# ASR-2DF.net
KiCad netlist of a schematic drawn in Altium Designer
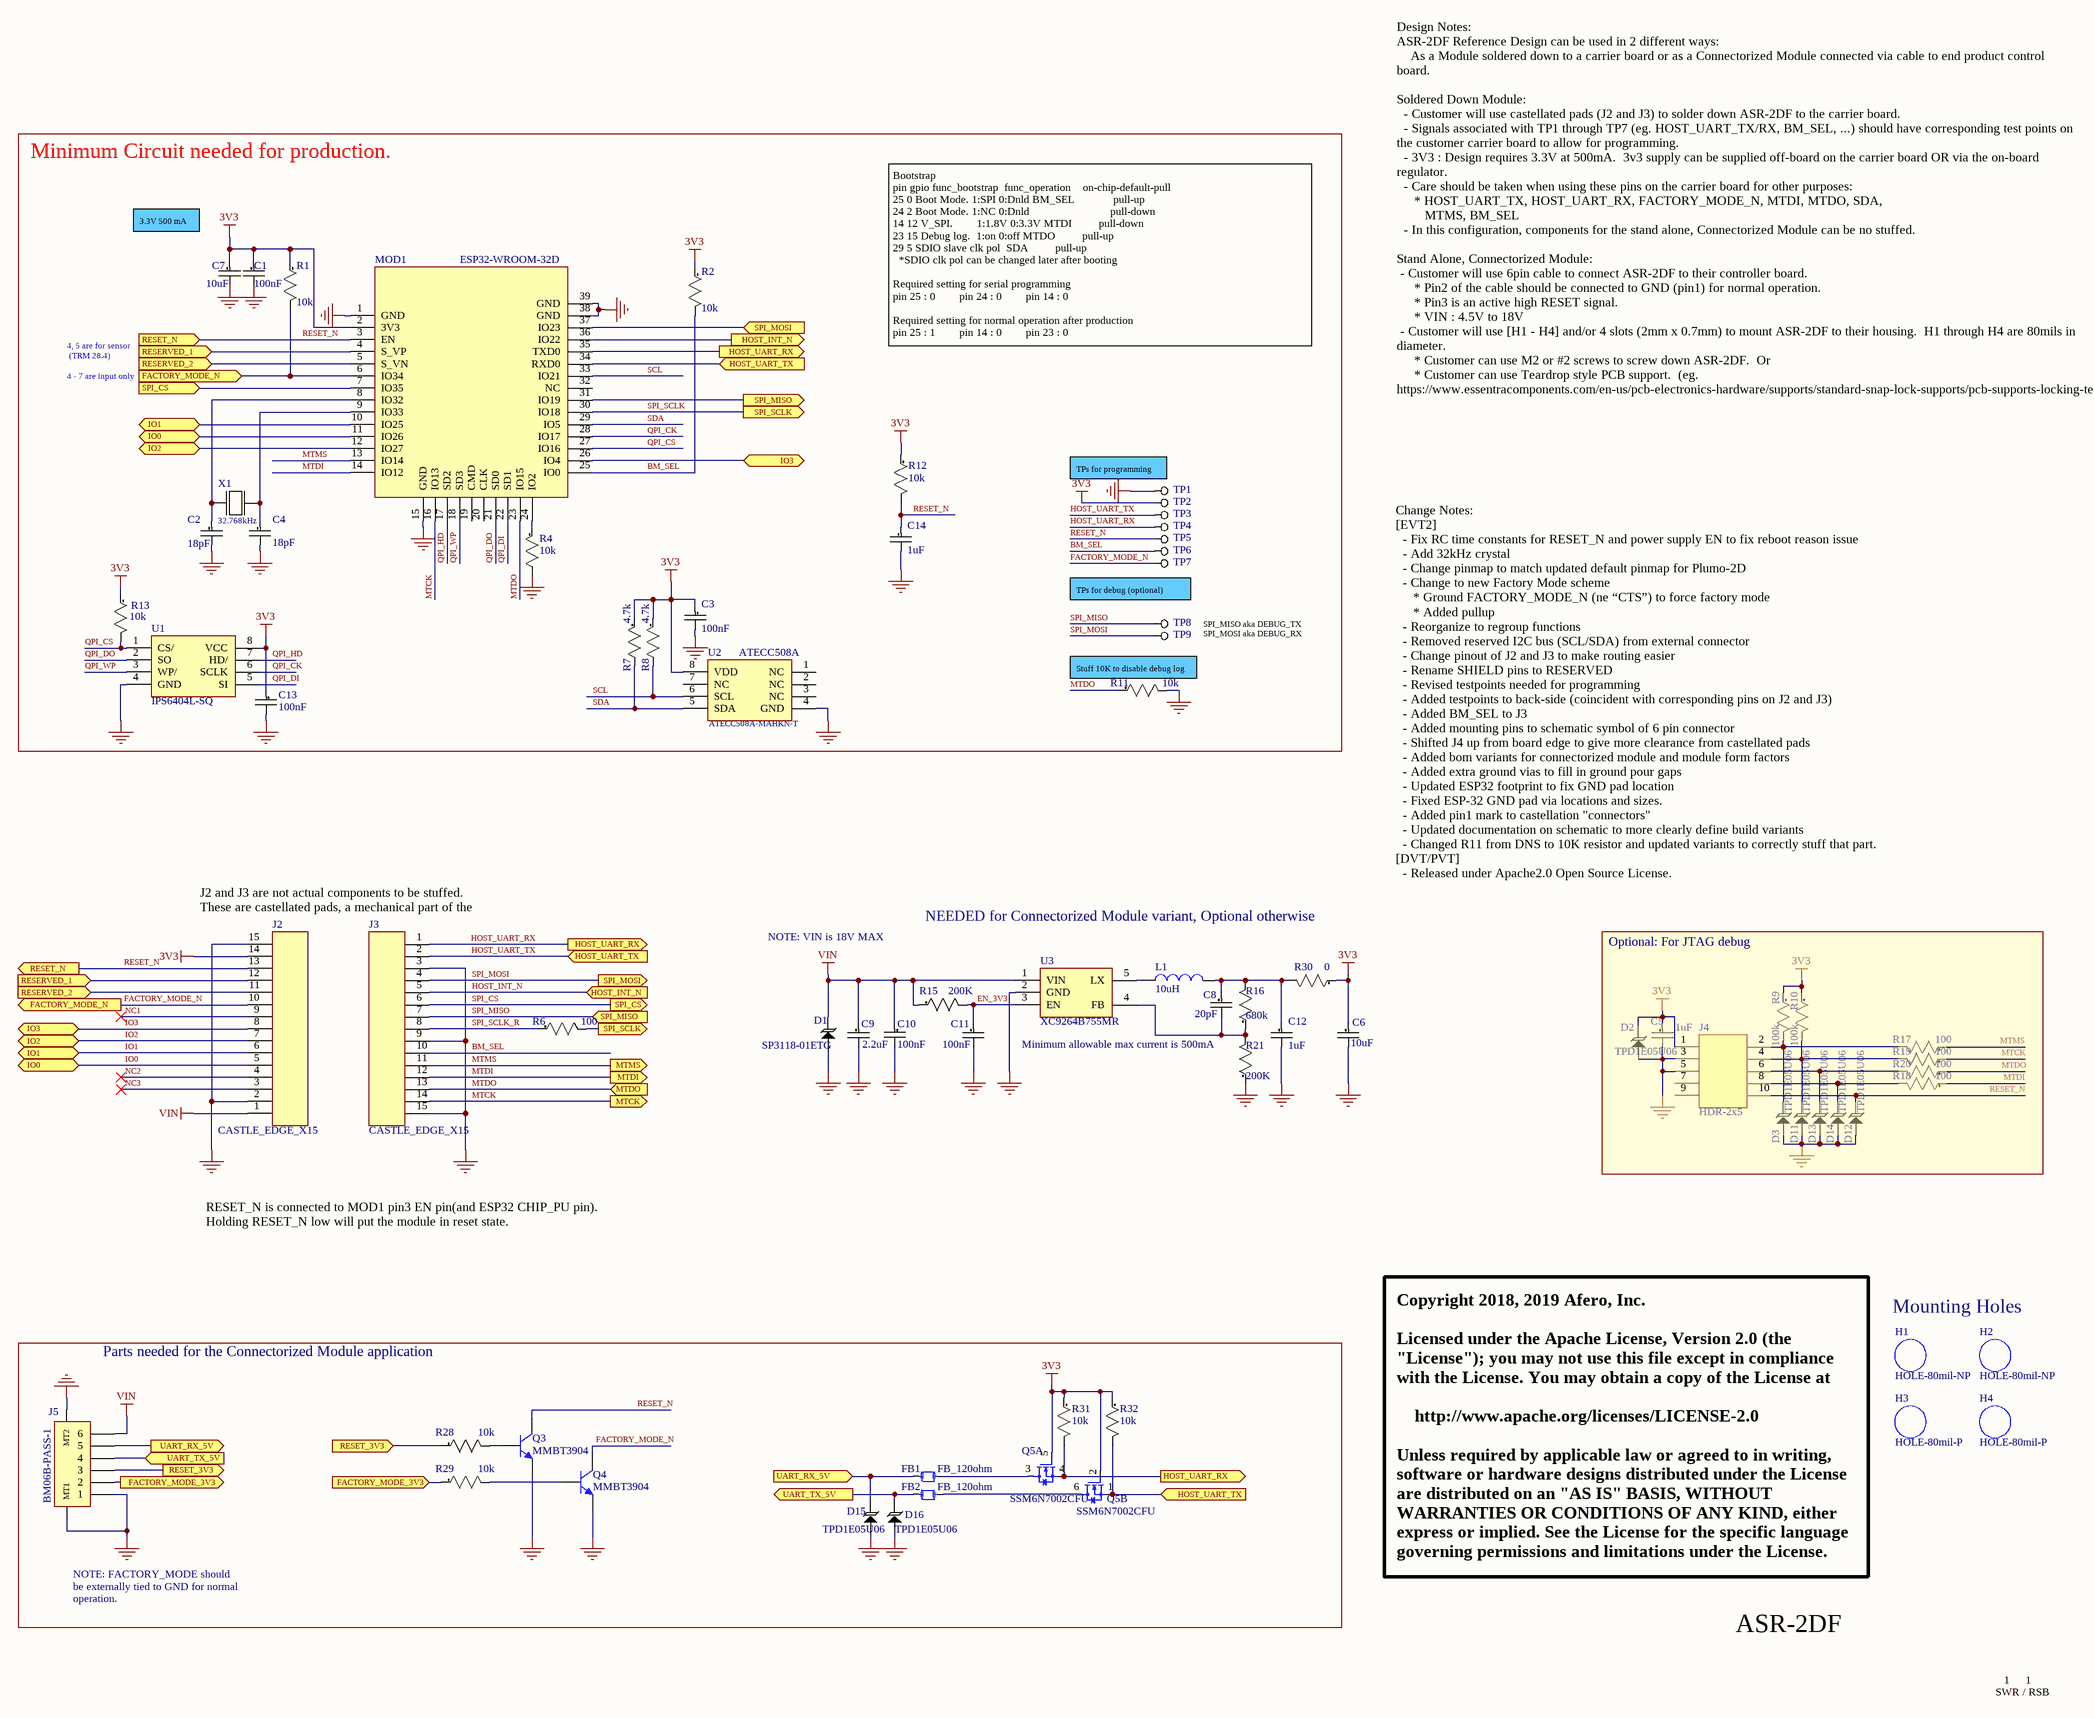
[diagram p0: ASR-2DF.SchDoc]

(export (version "E")
  (design (tool "Eeschema 10.0.6"))
  (components
    (comp (ref "C1")
      (value "100nF")
      (footprint "0402C-GENERIC")
      (description "Capacitor 100nF X5R 50V 10% 0402")
      (fields
        (field (name "MANUFACTURER") "Murata")
        (field (name "MANUFACTURER PART NUMBER") "GRM155R61H104KE19D")
      )
      (libsource (lib "ASR-2DF") (part "0402C-100n"))
    )
    (comp (ref "C2")
      (value "18pF")
      (footprint "0402C-GENERIC")
      (description "Capacitor, 18pF, 50V, 1%, C0G")
      (fields
        (field (name "MANUFACTURER") "Murata")
        (field (name "MANUFACTURER PART NUMBER") "GJM1555C1H180FB01D")
      )
      (libsource (lib "ASR-2DF") (part "0402C-18p"))
    )
    (comp (ref "C3")
      (value "100nF")
      (footprint "0402C-GENERIC")
      (description "Capacitor 100nF X5R 50V 10% 0402")
      (fields
        (field (name "MANUFACTURER") "Murata")
        (field (name "MANUFACTURER PART NUMBER") "GRM155R61H104KE19D")
      )
      (libsource (lib "ASR-2DF") (part "0402C-100n"))
    )
    (comp (ref "C4")
      (value "18pF")
      (footprint "0402C-GENERIC")
      (description "Capacitor, 18pF, 50V, 1%, C0G")
      (fields
        (field (name "MANUFACTURER") "Murata")
        (field (name "MANUFACTURER PART NUMBER") "GJM1555C1H180FB01D")
      )
      (libsource (lib "ASR-2DF") (part "0402C-18p"))
    )
    (comp (ref "C5")
      (value "1uF")
      (footprint "0402C-GENERIC")
      (description "Capacitor 1uF X5R 6.3V 20% 0402")
      (fields (field (name "MANUFACTURER") "SEM") (field (name "MANUFACTURER PART NUMBER") "CL05A105KQ5NNNC"))
      (libsource (lib "ASR-2DF") (part "0402C-1u"))
    )
    (comp (ref "C6")
      (value "10uF")
      (footprint "0603C-GENERIC")
      (description "Capacitor 10uF X5R 16V 20% 0603")
      (fields
        (field (name "MANUFACTURER") "Murata")
        (field (name "MANUFACTURER PART NUMBER") "GRM188R61C106MA73D")
      )
      (libsource (lib "ASR-2DF") (part "0603C-10u"))
    )
    (comp (ref "C7")
      (value "10uF")
      (footprint "0603C-GENERIC")
      (description "Capacitor 10uF X5R 16V 20% 0603")
      (fields
        (field (name "MANUFACTURER") "Murata")
        (field (name "MANUFACTURER PART NUMBER") "GRM188R61C106MA73D")
      )
      (libsource (lib "ASR-2DF") (part "0603C-10u"))
    )
    (comp (ref "C8")
      (value "20pF")
      (footprint "0402C-GENERIC")
      (description "Capacitor 20pF C0G 50V 1% 0402")
      (fields
        (field (name "MANUFACTURER") "Murata")
        (field (name "MANUFACTURER PART NUMBER") "GJM1555C1H200FB01D")
      )
      (libsource (lib "ASR-2DF") (part "0402C-20p"))
    )
    (comp (ref "C9")
      (value "2.2uF")
      (footprint "0603C-GENERIC")
      (description "Capacitor 2.2uF X5R 25V 10% 0603")
      (fields
        (field (name "MANUFACTURER") "Murata")
        (field (name "MANUFACTURER PART NUMBER") "GRM188R61E225KA12D")
      )
      (libsource (lib "ASR-2DF") (part "0603C-2u2"))
    )
    (comp (ref "C10")
      (value "100nF")
      (footprint "0402C-GENERIC")
      (description "Capacitor 100nF X5R 50V 10% 0402")
      (fields
        (field (name "MANUFACTURER") "Murata")
        (field (name "MANUFACTURER PART NUMBER") "GRM155R61H104KE19D")
      )
      (libsource (lib "ASR-2DF") (part "0402C-100n"))
    )
    (comp (ref "C11")
      (value "100nF")
      (footprint "0402C-GENERIC")
      (description "Capacitor 100nF X5R 50V 10% 0402")
      (fields
        (field (name "MANUFACTURER") "Murata")
        (field (name "MANUFACTURER PART NUMBER") "GRM155R61H104KE19D")
      )
      (libsource (lib "ASR-2DF") (part "0402C-100n"))
    )
    (comp (ref "C12")
      (value "1uF")
      (footprint "0402C-GENERIC")
      (description "Capacitor 1uF X5R 6.3V 20% 0402")
      (fields (field (name "MANUFACTURER") "SEM") (field (name "MANUFACTURER PART NUMBER") "CL05A105KQ5NNNC"))
      (libsource (lib "ASR-2DF") (part "0402C-1u"))
    )
    (comp (ref "C13")
      (value "100nF")
      (footprint "0402C-GENERIC")
      (description "Capacitor 100nF X5R 50V 10% 0402")
      (fields
        (field (name "MANUFACTURER") "Murata")
        (field (name "MANUFACTURER PART NUMBER") "GRM155R61H104KE19D")
      )
      (libsource (lib "ASR-2DF") (part "0402C-100n"))
    )
    (comp (ref "C14")
      (value "1uF")
      (footprint "0402C-GENERIC")
      (description "Capacitor 1uF X5R 6.3V 20% 0402")
      (fields (field (name "MANUFACTURER") "SEM") (field (name "MANUFACTURER PART NUMBER") "CL05A105KQ5NNNC"))
      (libsource (lib "ASR-2DF") (part "0402C-1u"))
    )
    (comp (ref "D1")
      (value "SP3118-01ETG")
      (footprint "SOD882")
      (description "Diode TVS")
      (fields (field (name "MANUFACTURER") "Littelfuse"))
      (libsource (lib "ASR-2DF") (part "SP3118-01ETG"))
    )
    (comp (ref "D2")
      (value "TPD1E05U06")
      (footprint "SON70P100X45-2N")
      (description "Diode TVS")
      (fields
        (field (name "MANUFACTURER") "Texas Instruments")
        (field (name "MANUFACTURER PART NUMBER") "TPD1E05U06DPYR")
      )
      (libsource (lib "ASR-2DF") (part "TPD1E05U06"))
    )
    (comp (ref "D3")
      (value "TPD1E05U06")
      (footprint "SON70P100X45-2N")
      (description "Diode TVS")
      (fields
        (field (name "MANUFACTURER") "Texas Instruments")
        (field (name "MANUFACTURER PART NUMBER") "TPD1E05U06DPYR")
      )
      (libsource (lib "ASR-2DF") (part "TPD1E05U06"))
    )
    (comp (ref "D11")
      (value "TPD1E05U06")
      (footprint "SON70P100X45-2N")
      (description "Diode TVS")
      (fields
        (field (name "MANUFACTURER") "Texas Instruments")
        (field (name "MANUFACTURER PART NUMBER") "TPD1E05U06DPYR")
      )
      (libsource (lib "ASR-2DF") (part "TPD1E05U06"))
    )
    (comp (ref "D12")
      (value "TPD1E05U06")
      (footprint "SON70P100X45-2N")
      (description "Diode TVS")
      (fields
        (field (name "MANUFACTURER") "Texas Instruments")
        (field (name "MANUFACTURER PART NUMBER") "TPD1E05U06DPYR")
      )
      (libsource (lib "ASR-2DF") (part "TPD1E05U06"))
    )
    (comp (ref "D13")
      (value "TPD1E05U06")
      (footprint "SON70P100X45-2N")
      (description "Diode TVS")
      (fields
        (field (name "MANUFACTURER") "Texas Instruments")
        (field (name "MANUFACTURER PART NUMBER") "TPD1E05U06DPYR")
      )
      (libsource (lib "ASR-2DF") (part "TPD1E05U06"))
    )
    (comp (ref "D14")
      (value "TPD1E05U06")
      (footprint "SON70P100X45-2N")
      (description "Diode TVS")
      (fields
        (field (name "MANUFACTURER") "Texas Instruments")
        (field (name "MANUFACTURER PART NUMBER") "TPD1E05U06DPYR")
      )
      (libsource (lib "ASR-2DF") (part "TPD1E05U06"))
    )
    (comp (ref "D15")
      (value "TPD1E05U06")
      (footprint "SON70P100X45-2N")
      (description "Diode TVS")
      (fields
        (field (name "MANUFACTURER") "Texas Instruments")
        (field (name "MANUFACTURER PART NUMBER") "TPD1E05U06DPYR")
      )
      (libsource (lib "ASR-2DF") (part "TPD1E05U06"))
    )
    (comp (ref "D16")
      (value "TPD1E05U06")
      (footprint "SON70P100X45-2N")
      (description "Diode TVS")
      (fields
        (field (name "MANUFACTURER") "Texas Instruments")
        (field (name "MANUFACTURER PART NUMBER") "TPD1E05U06DPYR")
      )
      (libsource (lib "ASR-2DF") (part "TPD1E05U06"))
    )
    (comp (ref "FB1")
      (value "FB_120ohm")
      (footprint "BLM15")
      (description "FERRITE BEAD 120OHM 0402 1LN")
      (fields
        (field (name "MANUFACTURER") "Murata")
        (field (name "MANUFACTURER PART NUMBER") "BLM15AG121SN1D")
      )
      (libsource (lib "ASR-2DF") (part "FB_120ohm"))
    )
    (comp (ref "FB2")
      (value "FB_120ohm")
      (footprint "BLM15")
      (description "FERRITE BEAD 120OHM 0402 1LN")
      (fields
        (field (name "MANUFACTURER") "Murata")
        (field (name "MANUFACTURER PART NUMBER") "BLM15AG121SN1D")
      )
      (libsource (lib "ASR-2DF") (part "FB_120ohm"))
    )
    (comp (ref "H1")
      (value "HOLE-80mil-NP")
      (footprint "HOLE-80mil-NP")
      (description "0.08\" Unplated Hole with 0.1\" keepout, #2 screw")
      (libsource (lib "ASR-2DF") (part "HOLE-80mil-NP"))
    )
    (comp (ref "H2")
      (value "HOLE-80mil-NP")
      (footprint "HOLE-80mil-NP")
      (description "0.08\" Unplated Hole with 0.1\" keepout, #2 screw")
      (libsource (lib "ASR-2DF") (part "HOLE-80mil-NP"))
    )
    (comp (ref "H3")
      (value "HOLE-80mil-P")
      (footprint "HOLE-80mil-P")
      (description "0.08\" Plated Hole, #2 screw")
      (libsource (lib "ASR-2DF") (part "HOLE-80mil-P"))
    )
    (comp (ref "H4")
      (value "HOLE-80mil-P")
      (footprint "HOLE-80mil-P")
      (description "0.08\" Plated Hole, #2 screw")
      (libsource (lib "ASR-2DF") (part "HOLE-80mil-P"))
    )
    (comp (ref "J2")
      (value "CASTLE_EDGE_X15")
      (footprint "CASTL-1X15")
      (description "0.07\" castellated board edge connector 15 positions")
      (libsource (lib "") (part "CASTLE_EDGE_X15_1"))
    )
    (comp (ref "J3")
      (value "CASTLE_EDGE_X15")
      (footprint "CASTL-1X15")
      (description "0.07\" castellated board edge connector 15 positions")
      (libsource (lib "ASR-2DF") (part "CASTLE_EDGE_X15"))
    )
    (comp (ref "J4")
      (value "HDR-2x5")
      (footprint "S9015E-05")
      (description ".050 Male Header 2x5")
      (fields (field (name "MANUFACTURER PART NUMBER") "GRPB052VWVN-RC"))
      (libsource (lib "ASR-2DF") (part "HDR-2x5"))
    )
    (comp (ref "J5")
      (value "BM06B-PASS-1")
      (footprint "BM06B-PASS-1")
      (description "JST PA-Family Vertical Header 2mm")
      (fields
        (field (name "MANUFACTURER PART NUMBER") "BM06B-PASS-1-TFT")
        (field (name "MANUFACTURER") "JST")
      )
      (libsource (lib "ASR-2DF") (part "BM06B-PASS-1"))
    )
    (comp (ref "L1")
      (value "10uH")
      (footprint "ASPI-0315FS")
      (description "Inductor 10uH 1.1A 0.22ohm 20% 3x3")
      (fields
        (field (name "MANUFACTURER") "Abracon")
        (field (name "MANUFACTURER PART NUMBER") "ASPI-0315FS-100M")
      )
      (libsource (lib "ASR-2DF") (part "ASPI-0315FS-100M"))
    )
    (comp (ref "MOD1")
      (value "ESP32-WROOM-32D")
      (footprint "ESP32-WROOM-32D")
      (description "Module WIFI BLE ESP32-D0WD SPI Flash")
      (fields (field (name "MANUFACTURER") "Espressif"))
      (libsource (lib "ASR-2DF") (part "ESP32-WROOM-32D"))
    )
    (comp (ref "Q3")
      (value "MMBT3904")
      (footprint "sot23")
      (description "TR NPN BJT 200mA 40V")
      (fields
        (field (name "MANUFACTURER PART NUMBER") "MMBT3904LT1G")
        (field (name "MANUFACTURER") "On Semiconductor")
      )
      (libsource (lib "ASR-2DF") (part "MMBT3904"))
    )
    (comp (ref "Q4")
      (value "MMBT3904")
      (footprint "sot23")
      (description "TR NPN BJT 200mA 40V")
      (fields
        (field (name "MANUFACTURER PART NUMBER") "MMBT3904LT1G")
        (field (name "MANUFACTURER") "On Semiconductor")
      )
      (libsource (lib "ASR-2DF") (part "MMBT3904"))
    )
    (comp (ref "Q5")
      (value "SSM6N7002CFU")
      (footprint "SOT363")
      (description "TR 2xNFET 170mA 60V")
      (fields
        (field (name "MANUFACTURER PART NUMBER") "SSM6N7002CFU.LF")
        (field (name "MANUFACTURER") "Toshiba")
      )
      (libsource (lib "ASR-2DF") (part "SSM6N7002CFU"))
    )
    (comp (ref "R1")
      (value "10k")
      (footprint "0402R-GENERIC")
      (description "Resistor 10K 50V 5% 0402")
      (fields
        (field (name "MANUFACTURER") "Vishay Dale")
        (field (name "MANUFACTURER PART NUMBER") "CRCW040210K0JNED")
      )
      (libsource (lib "ASR-2DF") (part "0402R-10k"))
    )
    (comp (ref "R2")
      (value "10k")
      (footprint "0402R-GENERIC")
      (description "Resistor 10K 50V 5% 0402")
      (fields
        (field (name "MANUFACTURER") "Vishay Dale")
        (field (name "MANUFACTURER PART NUMBER") "CRCW040210K0JNED")
      )
      (libsource (lib "ASR-2DF") (part "0402R-10k"))
    )
    (comp (ref "R4")
      (value "10k")
      (footprint "0402R-GENERIC")
      (description "Resistor 10K 50V 5% 0402")
      (fields
        (field (name "MANUFACTURER") "Vishay Dale")
        (field (name "MANUFACTURER PART NUMBER") "CRCW040210K0JNED")
      )
      (libsource (lib "ASR-2DF") (part "0402R-10k"))
    )
    (comp (ref "R6")
      (value "100")
      (footprint "0402R-GENERIC")
      (description "Resistor 100R 50V 5% 0402")
      (fields
        (field (name "MANUFACTURER") "Panasonic")
        (field (name "MANUFACTURER PART NUMBER") "ERJ-2GEJ101X")
      )
      (libsource (lib "ASR-2DF") (part "0402R-100R"))
    )
    (comp (ref "R7")
      (value "4.7k")
      (footprint "0402R-GENERIC")
      (description "Resistor 4.7K 50V 5% 0402")
      (fields
        (field (name "MANUFACTURER") "Panasonic")
        (field (name "MANUFACTURER PART NUMBER") "ERJ-2GEJ472X")
      )
      (libsource (lib "ASR-2DF") (part "0402R-4k7"))
    )
    (comp (ref "R8")
      (value "4.7k")
      (footprint "0402R-GENERIC")
      (description "Resistor 4.7K 50V 5% 0402")
      (fields
        (field (name "MANUFACTURER") "Panasonic")
        (field (name "MANUFACTURER PART NUMBER") "ERJ-2GEJ472X")
      )
      (libsource (lib "ASR-2DF") (part "0402R-4k7"))
    )
    (comp (ref "R9")
      (value "100k")
      (footprint "0402R-GENERIC")
      (description "Resistor 100K 50V 5% 0402")
      (fields
        (field (name "MANUFACTURER") "Panasonic")
        (field (name "MANUFACTURER PART NUMBER") "ERJ-2GEJ104X")
      )
      (libsource (lib "ASR-2DF") (part "0402R-100k"))
    )
    (comp (ref "R10")
      (value "100k")
      (footprint "0402R-GENERIC")
      (description "Resistor 100K 50V 5% 0402")
      (fields
        (field (name "MANUFACTURER") "Panasonic")
        (field (name "MANUFACTURER PART NUMBER") "ERJ-2GEJ104X")
      )
      (libsource (lib "ASR-2DF") (part "0402R-100k"))
    )
    (comp (ref "R11")
      (value "10k")
      (footprint "0402R-GENERIC")
      (description "Resistor 10K 50V 5% 0402")
      (fields
        (field (name "MANUFACTURER") "Vishay Dale")
        (field (name "MANUFACTURER PART NUMBER") "CRCW040210K0JNED")
      )
      (libsource (lib "ASR-2DF") (part "0402R-10k"))
    )
    (comp (ref "R12")
      (value "10k")
      (footprint "0402R-GENERIC")
      (description "Resistor 10K 50V 5% 0402")
      (fields
        (field (name "MANUFACTURER") "Vishay Dale")
        (field (name "MANUFACTURER PART NUMBER") "CRCW040210K0JNED")
      )
      (libsource (lib "ASR-2DF") (part "0402R-10k"))
    )
    (comp (ref "R13")
      (value "10k")
      (footprint "0402R-GENERIC")
      (description "Resistor 10K 50V 5% 0402")
      (fields
        (field (name "MANUFACTURER") "Vishay Dale")
        (field (name "MANUFACTURER PART NUMBER") "CRCW040210K0JNED")
      )
      (libsource (lib "ASR-2DF") (part "0402R-10k"))
    )
    (comp (ref "R15")
      (value "200K")
      (footprint "0402R-GENERIC")
      (description "Resistor 200K 50V 1% 0402")
      (fields
        (field (name "MANUFACTURER") "Panasonic")
        (field (name "MANUFACTURER PART NUMBER") "ERJ-2RKF2003X")
      )
      (libsource (lib "ASR-2DF") (part "0402R-200k"))
    )
    (comp (ref "R16")
      (value "680k")
      (footprint "0402R-GENERIC")
      (description "Resistor 680K 50V 5% 0402")
      (fields
        (field (name "MANUFACTURER") "Panasonic")
        (field (name "MANUFACTURER PART NUMBER") "ERJ-2GEJ684X")
      )
      (libsource (lib "ASR-2DF") (part "0402R-680k"))
    )
    (comp (ref "R17")
      (value "100")
      (footprint "0402R-GENERIC")
      (description "Resistor 100R 50V 5% 0402")
      (fields
        (field (name "MANUFACTURER") "Panasonic")
        (field (name "MANUFACTURER PART NUMBER") "ERJ-2GEJ101X")
      )
      (libsource (lib "ASR-2DF") (part "0402R-100R"))
    )
    (comp (ref "R18")
      (value "100")
      (footprint "0402R-GENERIC")
      (description "Resistor 100R 50V 5% 0402")
      (fields
        (field (name "MANUFACTURER") "Panasonic")
        (field (name "MANUFACTURER PART NUMBER") "ERJ-2GEJ101X")
      )
      (libsource (lib "ASR-2DF") (part "0402R-100R"))
    )
    (comp (ref "R19")
      (value "100")
      (footprint "0402R-GENERIC")
      (description "Resistor 100R 50V 5% 0402")
      (fields
        (field (name "MANUFACTURER") "Panasonic")
        (field (name "MANUFACTURER PART NUMBER") "ERJ-2GEJ101X")
      )
      (libsource (lib "ASR-2DF") (part "0402R-100R"))
    )
    (comp (ref "R20")
      (value "100")
      (footprint "0402R-GENERIC")
      (description "Resistor 100R 50V 5% 0402")
      (fields
        (field (name "MANUFACTURER") "Panasonic")
        (field (name "MANUFACTURER PART NUMBER") "ERJ-2GEJ101X")
      )
      (libsource (lib "ASR-2DF") (part "0402R-100R"))
    )
    (comp (ref "R21")
      (value "200K")
      (footprint "0402R-GENERIC")
      (description "Resistor 200K 50V 1% 0402")
      (fields
        (field (name "MANUFACTURER") "Panasonic")
        (field (name "MANUFACTURER PART NUMBER") "ERJ-2RKF2003X")
      )
      (libsource (lib "ASR-2DF") (part "0402R-200k"))
    )
    (comp (ref "R28")
      (value "10k")
      (footprint "0402R-GENERIC")
      (description "Resistor 10K 50V 5% 0402")
      (fields
        (field (name "MANUFACTURER") "Vishay Dale")
        (field (name "MANUFACTURER PART NUMBER") "CRCW040210K0JNED")
      )
      (libsource (lib "ASR-2DF") (part "0402R-10k"))
    )
    (comp (ref "R29")
      (value "10k")
      (footprint "0402R-GENERIC")
      (description "Resistor 10K 50V 5% 0402")
      (fields
        (field (name "MANUFACTURER") "Vishay Dale")
        (field (name "MANUFACTURER PART NUMBER") "CRCW040210K0JNED")
      )
      (libsource (lib "ASR-2DF") (part "0402R-10k"))
    )
    (comp (ref "R30")
      (value "0")
      (footprint "0402R-GENERIC")
      (description "Resistor 0R 50V 1% 0402")
      (fields
        (field (name "MANUFACTURER") "Yageo")
        (field (name "MANUFACTURER PART NUMBER") "RC0402FR-070RL")
      )
      (libsource (lib "ASR-2DF") (part "0402R-0R0"))
    )
    (comp (ref "R31")
      (value "10k")
      (footprint "0402R-GENERIC")
      (description "Resistor 10K 50V 5% 0402")
      (fields
        (field (name "MANUFACTURER") "Vishay Dale")
        (field (name "MANUFACTURER PART NUMBER") "CRCW040210K0JNED")
      )
      (libsource (lib "ASR-2DF") (part "0402R-10k"))
    )
    (comp (ref "R32")
      (value "10k")
      (footprint "0402R-GENERIC")
      (description "Resistor 10K 50V 5% 0402")
      (fields
        (field (name "MANUFACTURER") "Vishay Dale")
        (field (name "MANUFACTURER PART NUMBER") "CRCW040210K0JNED")
      )
      (libsource (lib "ASR-2DF") (part "0402R-10k"))
    )
    (comp (ref "TP1")
      (value "TP1MM")
      (footprint "TP1MM")
      (description "1mm Test Point")
      (libsource (lib "ASR-2DF") (part "TP1MM"))
    )
    (comp (ref "TP2")
      (value "TP1MM")
      (footprint "TP1MM")
      (description "1mm Test Point")
      (libsource (lib "ASR-2DF") (part "TP1MM"))
    )
    (comp (ref "TP3")
      (value "TP1MM")
      (footprint "TP1MM")
      (description "1mm Test Point")
      (libsource (lib "ASR-2DF") (part "TP1MM"))
    )
    (comp (ref "TP4")
      (value "TP1MM")
      (footprint "TP1MM")
      (description "1mm Test Point")
      (libsource (lib "ASR-2DF") (part "TP1MM"))
    )
    (comp (ref "TP5")
      (value "TP1MM")
      (footprint "TP1MM")
      (description "1mm Test Point")
      (libsource (lib "ASR-2DF") (part "TP1MM"))
    )
    (comp (ref "TP6")
      (value "TP1MM")
      (footprint "TP1MM")
      (description "1mm Test Point")
      (libsource (lib "ASR-2DF") (part "TP1MM"))
    )
    (comp (ref "TP7")
      (value "TP1MM")
      (footprint "TP1MM")
      (description "1mm Test Point")
      (libsource (lib "ASR-2DF") (part "TP1MM"))
    )
    (comp (ref "TP8")
      (value "TP1MM")
      (footprint "TP1MM")
      (description "1mm Test Point")
      (libsource (lib "ASR-2DF") (part "TP1MM"))
    )
    (comp (ref "TP9")
      (value "TP1MM")
      (footprint "TP1MM")
      (description "1mm Test Point")
      (libsource (lib "ASR-2DF") (part "TP1MM"))
    )
    (comp (ref "U1")
      (value "IPS6404L-SQ")
      (footprint "IPUS.PSRAM")
      (description "Memory SPI/QPI PSRAM 8MB SOIC8 150mil")
      (fields
        (field (name "MANUFACTURER") "IPUS")
        (field (name "MANUFACTURER PART NUMBER") "IPS6404L-SQ-SPN")
      )
      (libsource (lib "ASR-2DF") (part "IPS6404L-SQ"))
    )
    (comp (ref "U2")
      (value "ATECC508A")
      (footprint "SON50P300X60-8N")
      (description "Afero Custom CryptoAuthentication Device")
      (fields
        (field (name "MANUFACTURER") "Microchip / Atmel")
        (field (name "MANUFACTURER PART NUMBER") "ATECC508A-MAHKN-T")
      )
      (libsource (lib "ASR-2DF") (part "ATECC508A"))
    )
    (comp (ref "U3")
      (value "XC9264B755MR")
      (footprint "SOT95P275X130-5N")
      (description "Voltage Regulator 0.5A 500KHz Buck")
      (fields (field (name "MANUFACTURER") "Torex"))
      (libsource (lib "ASR-2DF") (part "XC9264B755MR"))
    )
    (comp (ref "X1")
      (value "32.768kHz")
      (footprint "ABS06")
      (description "Crystal, 32.768kHz ±20ppm")
      (fields
        (field (name "MANUFACTURER") "Abracon")
        (field (name "MANUFACTURER PART NUMBER") "ABS06-32.768KHZ-T")
      )
      (libsource (lib "ASR-2DF") (part "ABS06-32.768KHZ-T"))
    )
  )
  (nets
    (net (code "1") (name "/BM_SEL") (class "Default")
      (node (ref "J3") (pin "10") (pinfunction "10_10") (pintype "passive"))
      (node (ref "MOD1") (pin "25") (pinfunction "IO0_25") (pintype "passive"))
      (node (ref "R2") (pin "2") (pinfunction "2_2") (pintype "passive"))
      (node (ref "TP6") (pin "1") (pinfunction "1_1") (pintype "passive"))
    )
    (net (code "2") (name "/EN_3V3") (class "Default")
      (node (ref "C11") (pin "1") (pintype "passive"))
      (node (ref "R15") (pin "2") (pinfunction "2_2") (pintype "passive"))
      (node (ref "U3") (pin "3") (pinfunction "EN_3") (pintype "passive"))
    )
    (net (code "3") (name "/FACTORY_MODE_3V3") (class "Default")
      (node (ref "J5") (pin "2") (pinfunction "2_2") (pintype "passive"))
      (node (ref "R29") (pin "1") (pinfunction "1_1") (pintype "passive"))
    )
    (net (code "4") (name "/FACTORY_MODE_N") (class "Default")
      (node (ref "J2") (pin "10") (pinfunction "10_10") (pintype "passive"))
      (node (ref "MOD1") (pin "6") (pinfunction "IO34_6") (pintype "passive"))
      (node (ref "Q4") (pin "3") (pinfunction "C_3") (pintype "passive"))
      (node (ref "R1") (pin "2") (pinfunction "2_2") (pintype "passive"))
      (node (ref "TP7") (pin "1") (pinfunction "1_1") (pintype "passive"))
    )
    (net (code "5") (name "/HOST_INT_N") (class "Default")
      (node (ref "J3") (pin "5") (pinfunction "5_5") (pintype "passive"))
      (node (ref "MOD1") (pin "36") (pinfunction "IO22_36") (pintype "passive"))
    )
    (net (code "6") (name "/HOST_UART_RX") (class "Default")
      (node (ref "J3") (pin "1") (pinfunction "1_1") (pintype "passive"))
      (node (ref "MOD1") (pin "35") (pinfunction "TXD0_35") (pintype "passive"))
      (node (ref "Q5") (pin "4") (pinfunction "S2_4") (pintype "passive"))
      (node (ref "R31") (pin "2") (pinfunction "2_2") (pintype "passive"))
      (node (ref "TP4") (pin "1") (pinfunction "1_1") (pintype "passive"))
    )
    (net (code "7") (name "/HOST_UART_TX") (class "Default")
      (node (ref "J3") (pin "2") (pinfunction "2_2") (pintype "passive"))
      (node (ref "MOD1") (pin "34") (pinfunction "RXD0_34") (pintype "passive"))
      (node (ref "Q5") (pin "1") (pinfunction "S2_1") (pintype "passive"))
      (node (ref "R32") (pin "2") (pinfunction "2_2") (pintype "passive"))
      (node (ref "TP3") (pin "1") (pinfunction "1_1") (pintype "passive"))
    )
    (net (code "8") (name "/IO0") (class "Default")
      (node (ref "J2") (pin "5") (pinfunction "5_5") (pintype "passive"))
      (node (ref "MOD1") (pin "11") (pinfunction "IO26_11") (pintype "passive"))
    )
    (net (code "9") (name "/IO1") (class "Default")
      (node (ref "J2") (pin "6") (pinfunction "6_6") (pintype "passive"))
      (node (ref "MOD1") (pin "10") (pinfunction "IO25_10") (pintype "passive"))
    )
    (net (code "10") (name "/IO2") (class "Default")
      (node (ref "J2") (pin "7") (pinfunction "7_7") (pintype "passive"))
      (node (ref "MOD1") (pin "12") (pinfunction "IO27_12") (pintype "passive"))
    )
    (net (code "11") (name "/IO3") (class "Default")
      (node (ref "J2") (pin "8") (pinfunction "8_8") (pintype "passive"))
      (node (ref "MOD1") (pin "26") (pinfunction "IO4_26") (pintype "passive"))
    )
    (net (code "12") (name "/MTCK") (class "Default")
      (node (ref "J3") (pin "14") (pinfunction "14_14") (pintype "passive"))
      (node (ref "MOD1") (pin "16") (pinfunction "IO13_16") (pintype "passive"))
      (node (ref "R19") (pin "1") (pinfunction "1_1") (pintype "passive"))
    )
    (net (code "13") (name "/MTDI") (class "Default")
      (node (ref "J3") (pin "12") (pinfunction "12_12") (pintype "passive"))
      (node (ref "MOD1") (pin "14") (pinfunction "IO12_14") (pintype "passive"))
      (node (ref "R18") (pin "1") (pinfunction "1_1") (pintype "passive"))
    )
    (net (code "14") (name "/MTDO") (class "Default")
      (node (ref "J3") (pin "13") (pinfunction "13_13") (pintype "passive"))
      (node (ref "MOD1") (pin "23") (pinfunction "IO15_23") (pintype "passive"))
      (node (ref "R11") (pin "1") (pinfunction "1_1") (pintype "passive"))
      (node (ref "R20") (pin "1") (pinfunction "1_1") (pintype "passive"))
    )
    (net (code "15") (name "/MTMS") (class "Default")
      (node (ref "J3") (pin "11") (pinfunction "11_11") (pintype "passive"))
      (node (ref "MOD1") (pin "13") (pinfunction "IO14_13") (pintype "passive"))
      (node (ref "R17") (pin "1") (pinfunction "1_1") (pintype "passive"))
    )
    (net (code "16") (name "/NC1") (class "Default")
      (node (ref "J2") (pin "9") (pinfunction "9_9") (pintype "passive+no_connect"))
    )
    (net (code "17") (name "/NC2") (class "Default")
      (node (ref "J2") (pin "4") (pinfunction "4_4") (pintype "passive+no_connect"))
    )
    (net (code "18") (name "/NC3") (class "Default")
      (node (ref "J2") (pin "3") (pinfunction "3_3") (pintype "passive+no_connect"))
    )
    (net (code "19") (name "/QPI_CK") (class "Default")
      (node (ref "MOD1") (pin "28") (pinfunction "IO17_28") (pintype "passive"))
      (node (ref "U1") (pin "6") (pinfunction "SCLK_6") (pintype "passive"))
    )
    (net (code "20") (name "/QPI_CS") (class "Default")
      (node (ref "MOD1") (pin "27") (pinfunction "IO16_27") (pintype "passive"))
      (node (ref "R13") (pin "2") (pinfunction "2_2") (pintype "passive"))
      (node (ref "U1") (pin "1") (pinfunction "CS/_1") (pintype "passive"))
    )
    (net (code "21") (name "/QPI_DI") (class "Default")
      (node (ref "MOD1") (pin "22") (pinfunction "SD1_22") (pintype "passive"))
      (node (ref "U1") (pin "5") (pinfunction "SI_5") (pintype "passive"))
    )
    (net (code "22") (name "/QPI_DO") (class "Default")
      (node (ref "MOD1") (pin "21") (pinfunction "SD0_21") (pintype "passive"))
      (node (ref "U1") (pin "2") (pinfunction "SO_2") (pintype "passive"))
    )
    (net (code "23") (name "/QPI_HD") (class "Default")
      (node (ref "MOD1") (pin "17") (pinfunction "SD2_17") (pintype "passive"))
      (node (ref "U1") (pin "7") (pinfunction "HD/_7") (pintype "passive"))
    )
    (net (code "24") (name "/QPI_WP") (class "Default")
      (node (ref "MOD1") (pin "18") (pinfunction "SD3_18") (pintype "passive"))
      (node (ref "U1") (pin "3") (pinfunction "WP/_3") (pintype "passive"))
    )
    (net (code "25") (name "/RESERVED_1") (class "Default")
      (node (ref "J2") (pin "12") (pinfunction "12_12") (pintype "passive"))
      (node (ref "MOD1") (pin "4") (pinfunction "S_VP_4") (pintype "passive"))
    )
    (net (code "26") (name "/RESERVED_2") (class "Default")
      (node (ref "J2") (pin "11") (pinfunction "11_11") (pintype "passive"))
      (node (ref "MOD1") (pin "5") (pinfunction "S_VN_5") (pintype "passive"))
    )
    (net (code "27") (name "/RESET_3V3") (class "Default")
      (node (ref "J5") (pin "3") (pinfunction "3_3") (pintype "passive"))
      (node (ref "R28") (pin "1") (pinfunction "1_1") (pintype "passive"))
    )
    (net (code "28") (name "/RESET_N") (class "Default")
      (node (ref "C14") (pin "1") (pintype "passive"))
      (node (ref "D12") (pin "1") (pinfunction "I/O_1") (pintype "passive"))
      (node (ref "J2") (pin "13") (pinfunction "13_13") (pintype "passive"))
      (node (ref "J4") (pin "10") (pinfunction "10_10") (pintype "passive"))
      (node (ref "MOD1") (pin "3") (pinfunction "EN_3") (pintype "passive"))
      (node (ref "Q3") (pin "3") (pinfunction "C_3") (pintype "passive"))
      (node (ref "R12") (pin "2") (pinfunction "2_2") (pintype "passive"))
      (node (ref "TP5") (pin "1") (pinfunction "1_1") (pintype "passive"))
    )
    (net (code "29") (name "/SCL") (class "Default")
      (node (ref "MOD1") (pin "33") (pinfunction "IO21_33") (pintype "passive"))
      (node (ref "R8") (pin "2") (pinfunction "2_2") (pintype "passive"))
      (node (ref "U2") (pin "6") (pinfunction "SCL_6") (pintype "passive"))
    )
    (net (code "30") (name "/SDA") (class "Default")
      (node (ref "MOD1") (pin "29") (pinfunction "IO5_29") (pintype "passive"))
      (node (ref "R7") (pin "2") (pinfunction "2_2") (pintype "passive"))
      (node (ref "U2") (pin "5") (pinfunction "SDA_5") (pintype "passive"))
    )
    (net (code "31") (name "/SPI_CS") (class "Default")
      (node (ref "J3") (pin "6") (pinfunction "6_6") (pintype "passive"))
      (node (ref "MOD1") (pin "7") (pinfunction "IO35_7") (pintype "passive"))
    )
    (net (code "32") (name "/SPI_MISO") (class "Default")
      (node (ref "J3") (pin "7") (pinfunction "7_7") (pintype "passive"))
      (node (ref "MOD1") (pin "31") (pinfunction "IO19_31") (pintype "passive"))
      (node (ref "TP8") (pin "1") (pinfunction "1_1") (pintype "passive"))
    )
    (net (code "33") (name "/SPI_MOSI") (class "Default")
      (node (ref "J3") (pin "4") (pinfunction "4_4") (pintype "passive"))
      (node (ref "MOD1") (pin "37") (pinfunction "IO23_37") (pintype "passive"))
      (node (ref "TP9") (pin "1") (pinfunction "1_1") (pintype "passive"))
    )
    (net (code "34") (name "/SPI_SCLK") (class "Default")
      (node (ref "MOD1") (pin "30") (pinfunction "IO18_30") (pintype "passive"))
      (node (ref "R6") (pin "2") (pinfunction "2_2") (pintype "passive"))
    )
    (net (code "35") (name "/SPI_SCLK_R") (class "Default")
      (node (ref "J3") (pin "8") (pinfunction "8_8") (pintype "passive"))
      (node (ref "R6") (pin "1") (pinfunction "1_1") (pintype "passive"))
    )
    (net (code "36") (name "/UART_RX_5V") (class "Default")
      (node (ref "D15") (pin "1") (pinfunction "I/O_1") (pintype "passive"))
      (node (ref "FB1") (pin "1") (pinfunction "1_1") (pintype "passive"))
      (node (ref "J5") (pin "5") (pinfunction "5_5") (pintype "passive"))
    )
    (net (code "37") (name "/UART_TX_5V") (class "Default")
      (node (ref "D16") (pin "1") (pinfunction "I/O_1") (pintype "passive"))
      (node (ref "FB2") (pin "1") (pinfunction "1_1") (pintype "passive"))
      (node (ref "J5") (pin "4") (pinfunction "4_4") (pintype "passive"))
    )
    (net (code "38") (name "3V3") (class "Default")
      (node (ref "C1") (pin "1") (pintype "passive"))
      (node (ref "C13") (pin "1") (pintype "passive"))
      (node (ref "C3") (pin "1") (pintype "passive"))
      (node (ref "C5") (pin "1") (pintype "passive"))
      (node (ref "C6") (pin "1") (pintype "passive"))
      (node (ref "C7") (pin "1") (pintype "passive"))
      (node (ref "D2") (pin "1") (pinfunction "I/O_1") (pintype "passive"))
      (node (ref "J2") (pin "14") (pinfunction "14_14") (pintype "passive"))
      (node (ref "J4") (pin "1") (pinfunction "1_1") (pintype "passive"))
      (node (ref "MOD1") (pin "2") (pinfunction "3V3_2") (pintype "passive"))
      (node (ref "Q5") (pin "2") (pinfunction "G2_2") (pintype "passive"))
      (node (ref "Q5") (pin "5") (pinfunction "G2_5") (pintype "passive"))
      (node (ref "R1") (pin "1") (pinfunction "1_1") (pintype "passive"))
      (node (ref "R10") (pin "1") (pinfunction "1_1") (pintype "passive"))
      (node (ref "R12") (pin "1") (pinfunction "1_1") (pintype "passive"))
      (node (ref "R13") (pin "1") (pinfunction "1_1") (pintype "passive"))
      (node (ref "R2") (pin "1") (pinfunction "1_1") (pintype "passive"))
      (node (ref "R30") (pin "1") (pinfunction "1_1") (pintype "passive"))
      (node (ref "R31") (pin "1") (pinfunction "1_1") (pintype "passive"))
      (node (ref "R32") (pin "1") (pinfunction "1_1") (pintype "passive"))
      (node (ref "R7") (pin "1") (pinfunction "1_1") (pintype "passive"))
      (node (ref "R8") (pin "1") (pinfunction "1_1") (pintype "passive"))
      (node (ref "R9") (pin "1") (pinfunction "1_1") (pintype "passive"))
      (node (ref "TP2") (pin "1") (pinfunction "1_1") (pintype "passive"))
      (node (ref "U1") (pin "8") (pinfunction "VCC_8") (pintype "passive"))
      (node (ref "U2") (pin "8") (pinfunction "VDD_8") (pintype "power_in"))
    )
    (net (code "39") (name "GND") (class "Default")
      (node (ref "C1") (pin "2") (pintype "passive"))
      (node (ref "C10") (pin "2") (pintype "passive"))
      (node (ref "C11") (pin "2") (pintype "passive"))
      (node (ref "C12") (pin "2") (pintype "passive"))
      (node (ref "C13") (pin "2") (pintype "passive"))
      (node (ref "C14") (pin "2") (pintype "passive"))
      (node (ref "C2") (pin "2") (pintype "passive"))
      (node (ref "C3") (pin "2") (pintype "passive"))
      (node (ref "C4") (pin "2") (pintype "passive"))
      (node (ref "C5") (pin "2") (pintype "passive"))
      (node (ref "C6") (pin "2") (pintype "passive"))
      (node (ref "C7") (pin "2") (pintype "passive"))
      (node (ref "C9") (pin "2") (pintype "passive"))
      (node (ref "D1") (pin "2") (pinfunction "GND_2") (pintype "passive"))
      (node (ref "D11") (pin "2") (pinfunction "GND_2") (pintype "passive"))
      (node (ref "D12") (pin "2") (pinfunction "GND_2") (pintype "passive"))
      (node (ref "D13") (pin "2") (pinfunction "GND_2") (pintype "passive"))
      (node (ref "D14") (pin "2") (pinfunction "GND_2") (pintype "passive"))
      (node (ref "D15") (pin "2") (pinfunction "GND_2") (pintype "passive"))
      (node (ref "D16") (pin "2") (pinfunction "GND_2") (pintype "passive"))
      (node (ref "D2") (pin "2") (pinfunction "GND_2") (pintype "passive"))
      (node (ref "D3") (pin "2") (pinfunction "GND_2") (pintype "passive"))
      (node (ref "J2") (pin "15") (pinfunction "15_15") (pintype "passive"))
      (node (ref "J2") (pin "2") (pinfunction "2_2") (pintype "passive"))
      (node (ref "J3") (pin "15") (pinfunction "15_15") (pintype "passive"))
      (node (ref "J3") (pin "3") (pinfunction "3_3") (pintype "passive"))
      (node (ref "J3") (pin "9") (pinfunction "9_9") (pintype "passive"))
      (node (ref "J4") (pin "3") (pinfunction "3_3") (pintype "passive"))
      (node (ref "J4") (pin "5") (pinfunction "5_5") (pintype "passive"))
      (node (ref "J5") (pin "1") (pinfunction "1_1") (pintype "passive"))
      (node (ref "J5") (pin "7") (pinfunction "MT1_7") (pintype "passive"))
      (node (ref "J5") (pin "8") (pinfunction "MT2_8") (pintype "passive"))
      (node (ref "MOD1") (pin "1") (pinfunction "GND_1") (pintype "passive"))
      (node (ref "MOD1") (pin "15") (pinfunction "GND_15") (pintype "passive"))
      (node (ref "MOD1") (pin "38") (pinfunction "GND_38") (pintype "passive"))
      (node (ref "MOD1") (pin "39") (pinfunction "GND_39") (pintype "passive"))
      (node (ref "Q3") (pin "2") (pinfunction "E_2") (pintype "passive"))
      (node (ref "Q4") (pin "2") (pinfunction "E_2") (pintype "passive"))
      (node (ref "R11") (pin "2") (pinfunction "2_2") (pintype "passive"))
      (node (ref "R21") (pin "1") (pinfunction "1_1") (pintype "passive"))
      (node (ref "R4") (pin "2") (pinfunction "2_2") (pintype "passive"))
      (node (ref "TP1") (pin "1") (pinfunction "1_1") (pintype "passive"))
      (node (ref "U1") (pin "4") (pinfunction "GND_4") (pintype "passive"))
      (node (ref "U2") (pin "4") (pinfunction "GND_4") (pintype "power_in"))
      (node (ref "U3") (pin "2") (pinfunction "GND_2") (pintype "power_in"))
    )
    (net (code "40") (name "Net-(C12-Pad1)") (class "Default")
      (node (ref "C12") (pin "1") (pintype "passive"))
      (node (ref "C8") (pin "1") (pintype "passive"))
      (node (ref "L1") (pin "2") (pinfunction "2_2") (pintype "passive"))
      (node (ref "R16") (pin "2") (pinfunction "2_2") (pintype "passive"))
      (node (ref "R30") (pin "2") (pinfunction "2_2") (pintype "passive"))
    )
    (net (code "41") (name "Net-(D3-I{slash}O)") (class "Default")
      (node (ref "D3") (pin "1") (pinfunction "I/O_1") (pintype "passive"))
      (node (ref "J4") (pin "2") (pinfunction "2_2") (pintype "passive"))
      (node (ref "R17") (pin "2") (pinfunction "2_2") (pintype "passive"))
      (node (ref "R9") (pin "2") (pinfunction "2_2") (pintype "passive"))
    )
    (net (code "42") (name "Net-(D11-I{slash}O)") (class "Default")
      (node (ref "D11") (pin "1") (pinfunction "I/O_1") (pintype "passive"))
      (node (ref "J4") (pin "4") (pinfunction "4_4") (pintype "passive"))
      (node (ref "R10") (pin "2") (pinfunction "2_2") (pintype "passive"))
      (node (ref "R19") (pin "2") (pinfunction "2_2") (pintype "passive"))
    )
    (net (code "43") (name "Net-(D13-I{slash}O)") (class "Default")
      (node (ref "D13") (pin "1") (pinfunction "I/O_1") (pintype "passive"))
      (node (ref "J4") (pin "6") (pinfunction "6_6") (pintype "passive"))
      (node (ref "R20") (pin "2") (pinfunction "2_2") (pintype "passive"))
    )
    (net (code "44") (name "Net-(D14-I{slash}O)") (class "Default")
      (node (ref "D14") (pin "1") (pinfunction "I/O_1") (pintype "passive"))
      (node (ref "J4") (pin "8") (pinfunction "8_8") (pintype "passive"))
      (node (ref "R18") (pin "2") (pinfunction "2_2") (pintype "passive"))
    )
    (net (code "45") (name "Net-(MOD1-IO2)") (class "Default")
      (node (ref "MOD1") (pin "24") (pinfunction "IO2_24") (pintype "passive"))
      (node (ref "R4") (pin "1") (pinfunction "1_1") (pintype "passive"))
    )
    (net (code "46") (name "Net-(MOD1-IO32)") (class "Default")
      (node (ref "C2") (pin "1") (pintype "passive"))
      (node (ref "MOD1") (pin "8") (pinfunction "IO32_8") (pintype "passive"))
      (node (ref "X1") (pin "2") (pinfunction "2_2") (pintype "passive"))
    )
    (net (code "47") (name "Net-(MOD1-IO33)") (class "Default")
      (node (ref "C4") (pin "1") (pintype "passive"))
      (node (ref "MOD1") (pin "9") (pinfunction "IO33_9") (pintype "passive"))
      (node (ref "X1") (pin "1") (pinfunction "1_1") (pintype "passive"))
    )
    (net (code "48") (name "Net-(Q3-B)") (class "Default")
      (node (ref "Q3") (pin "1") (pinfunction "B_1") (pintype "passive"))
      (node (ref "R28") (pin "2") (pinfunction "2_2") (pintype "passive"))
    )
    (net (code "49") (name "Net-(Q4-B)") (class "Default")
      (node (ref "Q4") (pin "1") (pinfunction "B_1") (pintype "passive"))
      (node (ref "R29") (pin "2") (pinfunction "2_2") (pintype "passive"))
    )
    (net (code "50") (name "Net-(Q5A-D2)") (class "Default")
      (node (ref "FB1") (pin "2") (pinfunction "2_2") (pintype "passive"))
      (node (ref "Q5") (pin "3") (pinfunction "D2_3") (pintype "passive"))
    )
    (net (code "51") (name "Net-(Q5B-D2)") (class "Default")
      (node (ref "FB2") (pin "2") (pinfunction "2_2") (pintype "passive"))
      (node (ref "Q5") (pin "6") (pinfunction "D2_6") (pintype "passive"))
    )
    (net (code "52") (name "Net-(U3-FB)") (class "Default")
      (node (ref "C8") (pin "2") (pintype "passive"))
      (node (ref "R16") (pin "1") (pinfunction "1_1") (pintype "passive"))
      (node (ref "R21") (pin "2") (pinfunction "2_2") (pintype "passive"))
      (node (ref "U3") (pin "4") (pinfunction "FB_4") (pintype "passive"))
    )
    (net (code "53") (name "Net-(U3-LX)") (class "Default")
      (node (ref "L1") (pin "1") (pinfunction "1_1") (pintype "passive"))
      (node (ref "U3") (pin "5") (pinfunction "LX_5") (pintype "passive"))
    )
    (net (code "54") (name "VIN") (class "Default")
      (node (ref "C10") (pin "1") (pintype "passive"))
      (node (ref "C9") (pin "1") (pintype "passive"))
      (node (ref "D1") (pin "1") (pinfunction "I/O_1") (pintype "passive"))
      (node (ref "J2") (pin "1") (pinfunction "1_1") (pintype "passive"))
      (node (ref "J5") (pin "6") (pinfunction "6_6") (pintype "passive"))
      (node (ref "R15") (pin "1") (pinfunction "1_1") (pintype "passive"))
      (node (ref "U3") (pin "1") (pinfunction "VIN_1") (pintype "power_in"))
    )
    (net (code "55") (name "unconnected-(J4-Pad7)") (class "Default")
      (node (ref "J4") (pin "7") (pinfunction "7_7") (pintype "passive"))
    )
    (net (code "56") (name "unconnected-(J4-Pad9)") (class "Default")
      (node (ref "J4") (pin "9") (pinfunction "9_9") (pintype "passive"))
    )
    (net (code "57") (name "unconnected-(MOD1-CLK-Pad20)") (class "Default")
      (node (ref "MOD1") (pin "20") (pinfunction "CLK_20") (pintype "passive"))
    )
    (net (code "58") (name "unconnected-(MOD1-CMD-Pad19)") (class "Default")
      (node (ref "MOD1") (pin "19") (pinfunction "CMD_19") (pintype "passive"))
    )
    (net (code "59") (name "unconnected-(MOD1-NC-Pad32)") (class "Default")
      (node (ref "MOD1") (pin "32") (pinfunction "NC_32") (pintype "passive"))
    )
    (net (code "60") (name "unconnected-(U2-NC-Pad1)") (class "Default")
      (node (ref "U2") (pin "1") (pinfunction "NC_1") (pintype "passive"))
    )
    (net (code "61") (name "unconnected-(U2-NC-Pad2)") (class "Default")
      (node (ref "U2") (pin "2") (pinfunction "NC_2") (pintype "passive"))
    )
    (net (code "62") (name "unconnected-(U2-NC-Pad3)") (class "Default")
      (node (ref "U2") (pin "3") (pinfunction "NC_3") (pintype "passive"))
    )
    (net (code "63") (name "unconnected-(U2-NC-Pad7)") (class "Default")
      (node (ref "U2") (pin "7") (pinfunction "NC_7") (pintype "passive"))
    )
  )
)
